# Main.net
KiCad netlist of a schematic drawn in Altium Designer
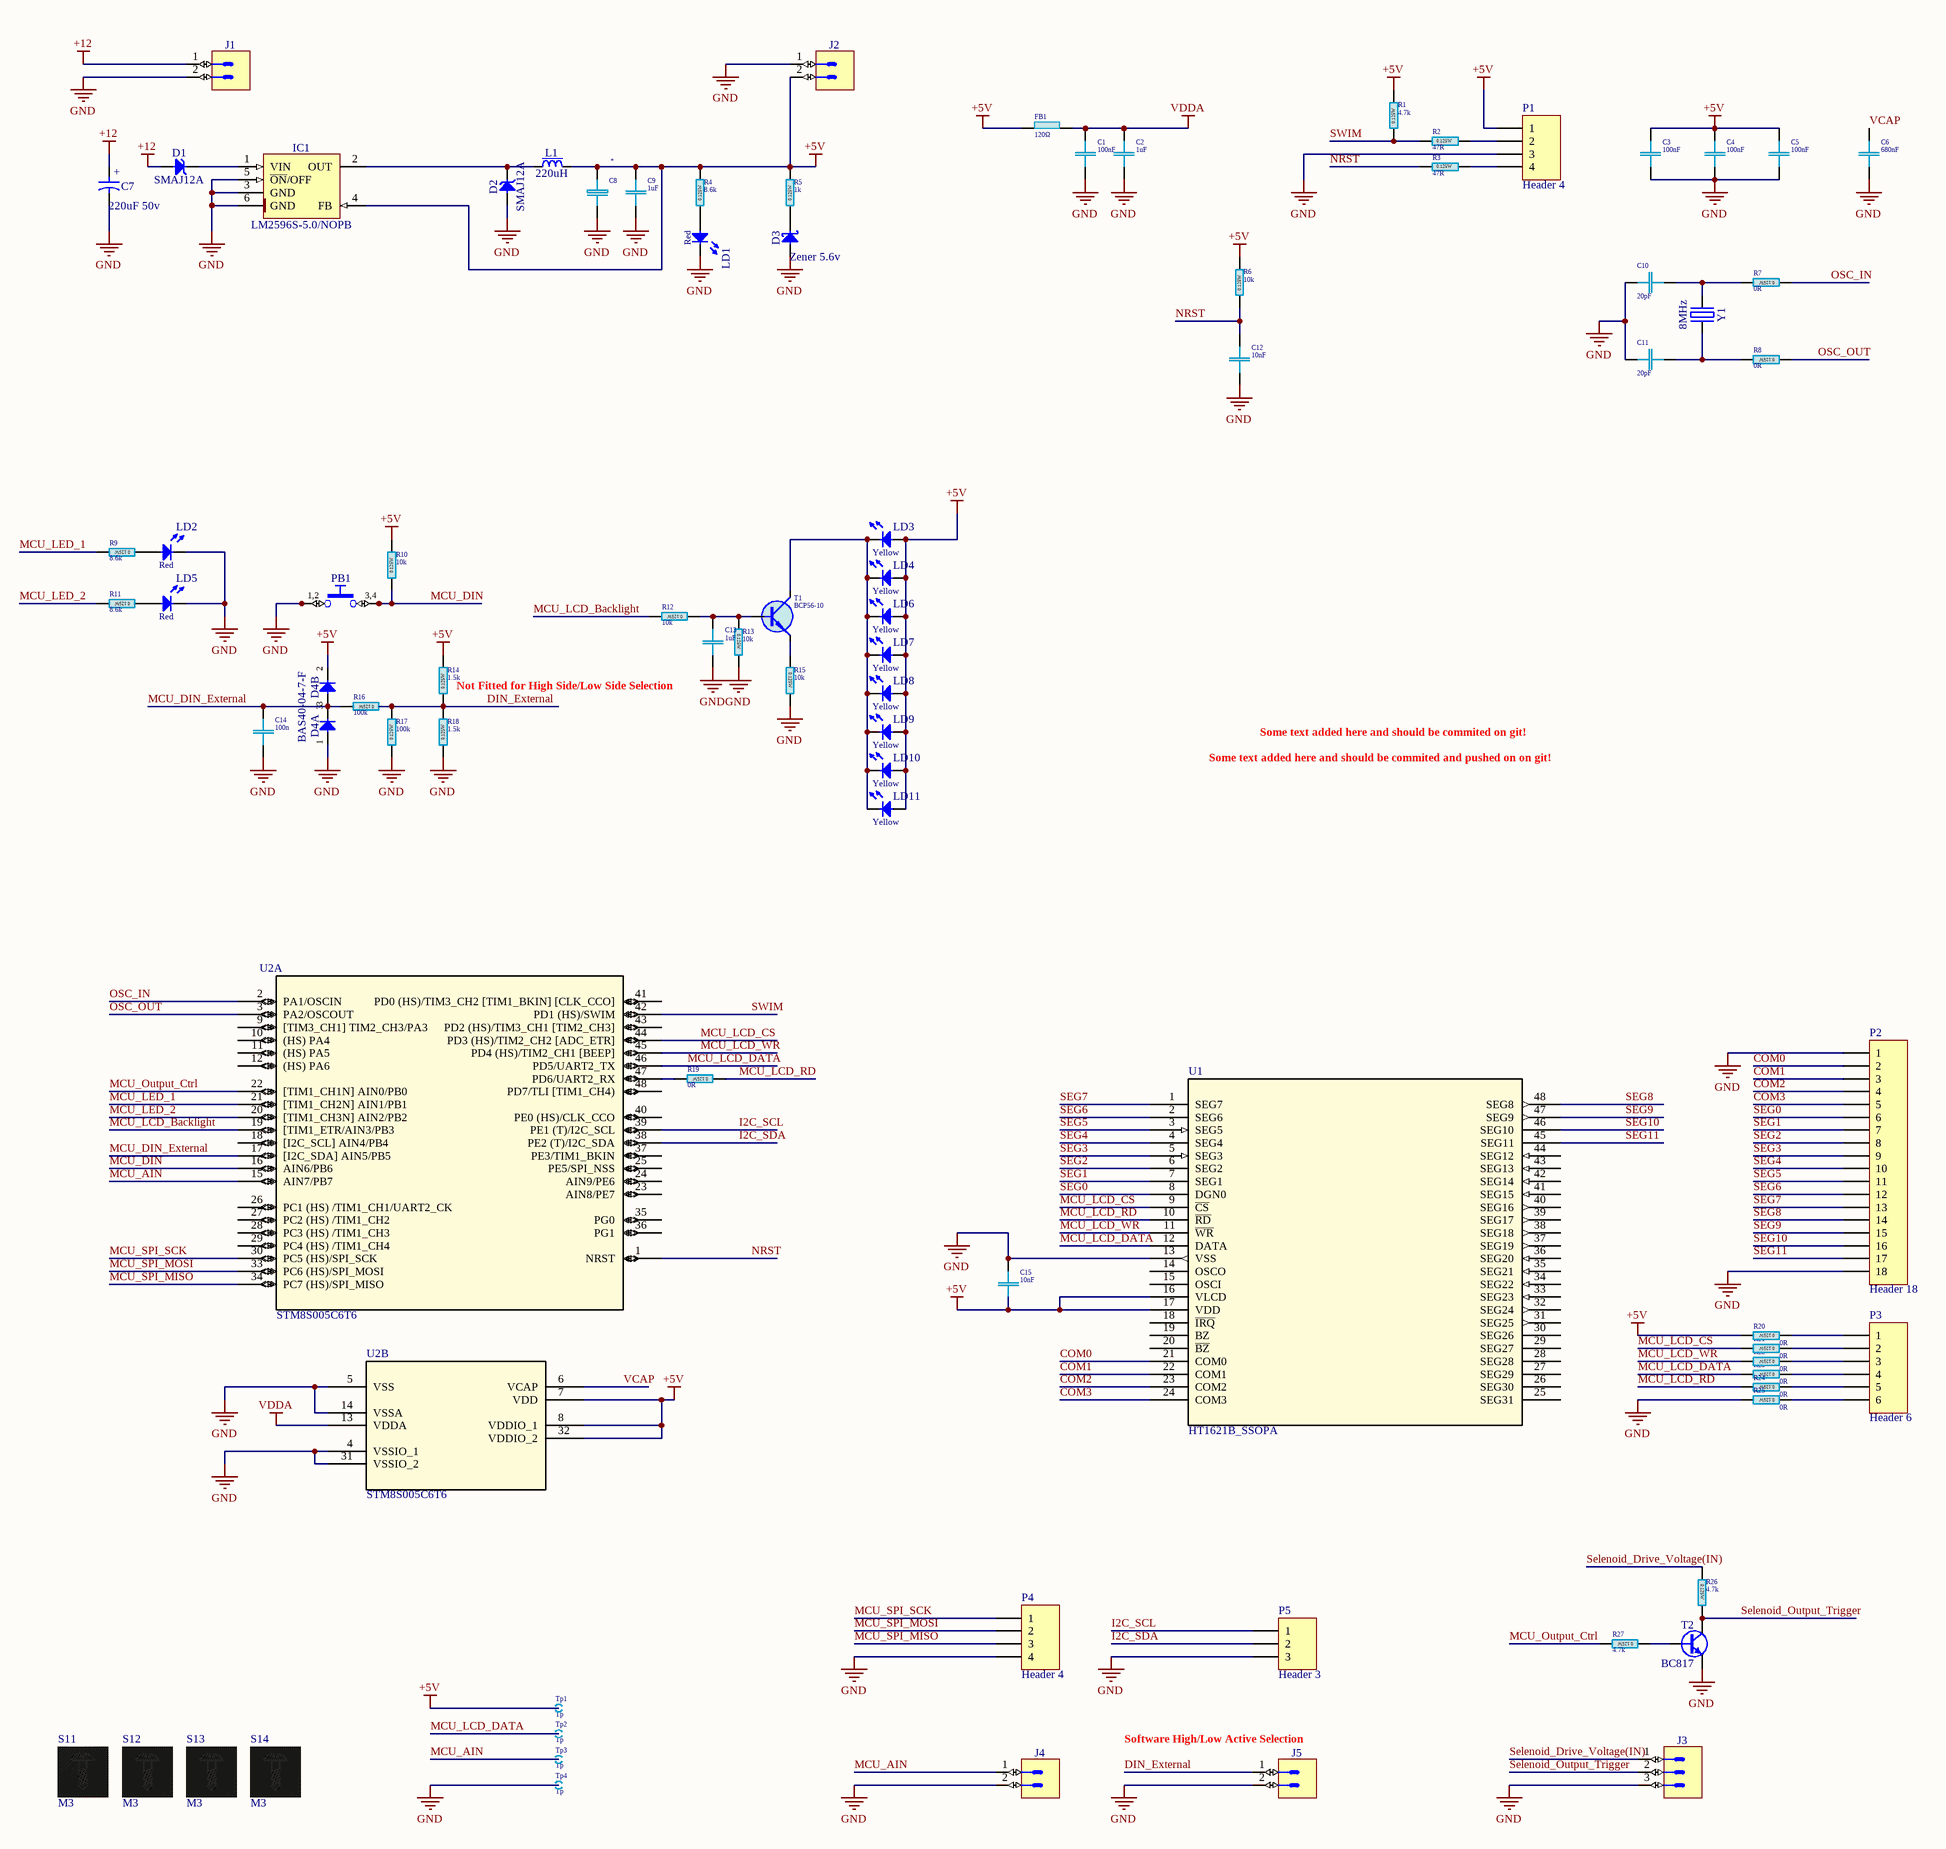
[diagram p0: Main.SchDoc]

(export (version "E")
  (design (tool "Eeschema 10.0.6"))
  (components
    (comp (ref "C1")
      (value "100nF")
      (footprint "C 0805(2012)x0.65")
      (description "SMD 0805     16V X7R 10%")
      (fields (field (name "MANUFACTURER") "Samsung"))
      (libsource (lib "SMD Passive") (part "C 0805    16V X7R - 0*"))
    )
    (comp (ref "C2")
      (value "1uF")
      (footprint "C 0805(2012)x0.65")
      (description "SMD 0805     50V X7R 10%")
      (fields (field (name "PART NUMBER") "CL21B105KBFNNNE") (field (name "MANUFACTURER") "Samsung"))
      (libsource (lib "SMD Passive") (part "C 0805    50V X7R - 1u"))
    )
    (comp (ref "C3")
      (value "100nF")
      (footprint "C 0805(2012)x0.65")
      (description "SMD 0805     16V X7R 10%")
      (fields (field (name "MANUFACTURER") "Samsung"))
      (libsource (lib "SMD Passive") (part "C 0805    16V X7R - 0*"))
    )
    (comp (ref "C4")
      (value "100nF")
      (footprint "C 0805(2012)x0.65")
      (description "SMD 0805     16V X7R 10%")
      (fields (field (name "MANUFACTURER") "Samsung"))
      (libsource (lib "SMD Passive") (part "C 0805    16V X7R - 0*"))
    )
    (comp (ref "C5")
      (value "100nF")
      (footprint "C 0805(2012)x0.65")
      (description "SMD 0805     16V X7R 10%")
      (fields (field (name "MANUFACTURER") "Samsung"))
      (libsource (lib "SMD Passive") (part "C 0805    16V X7R - 0*"))
    )
    (comp (ref "C6")
      (value "680nF")
      (footprint "C 0805(2012)x0.65")
      (description "SMD 0805     16V X7R 10%")
      (fields (field (name "MANUFACTURER") "Samsung"))
      (libsource (lib "SMD Passive") (part "C 0805    16V X7R - 0*"))
    )
    (comp (ref "C7")
      (value "220uF 50v")
      (footprint "CAPAE1030X1020N")
      (description "Polarised capacitor")
      (fields (field (name "PART NUMBER") "CAE1030-1020_220UF_50V_20%") (field (name "VOLTAGE") "50V"))
      (libsource (lib "Capacitors") (part "Capacitor - polarized"))
    )
    (comp (ref "C8")
      (value "*")
      (footprint "EL SMD D8 h10.5")
      (description "SMD D   8mm h10.5mm")
      (fields (field (name "MANUFACTURER") "Fujicon") (field (name "ALTIUM_VALUE") "*"))
      (libsource (lib "SMD Passive") (part "EL D   8mm h10.5mm"))
    )
    (comp (ref "C9")
      (value "1uF")
      (footprint "C 0805(2012)x0.65")
      (description "SMD 0805     50V X7R 10%")
      (fields (field (name "PART NUMBER") "CL21B105KBFNNNE") (field (name "MANUFACTURER") "Samsung"))
      (libsource (lib "SMD Passive") (part "C 0805    50V X7R - 1u"))
    )
    (comp (ref "C10")
      (value "20pF")
      (footprint "C 0805(2012)x0.65")
      (description "SMD 0805     16V X7R 10%")
      (fields (field (name "MANUFACTURER") "Samsung"))
      (libsource (lib "SMD Passive") (part "C 0805    16V X7R - 0*"))
    )
    (comp (ref "C11")
      (value "20pF")
      (footprint "C 0805(2012)x0.65")
      (description "SMD 0805     16V X7R 10%")
      (fields (field (name "MANUFACTURER") "Samsung"))
      (libsource (lib "SMD Passive") (part "C 0805    16V X7R - 0*"))
    )
    (comp (ref "C12")
      (value "10nF")
      (footprint "C 0805(2012)x0.65")
      (description "SMD 0805     16V X7R 10%")
      (fields (field (name "MANUFACTURER") "Samsung"))
      (libsource (lib "SMD Passive") (part "C 0805    16V X7R - 0*"))
    )
    (comp (ref "C13")
      (value "1uF")
      (footprint "C 0805(2012)x0.65")
      (description "SMD 0805     50V X7R 10%")
      (fields (field (name "PART NUMBER") "CL21B105KBFNNNE") (field (name "MANUFACTURER") "Samsung"))
      (libsource (lib "SMD Passive") (part "C 0805    50V X7R - 1u"))
    )
    (comp (ref "C14")
      (value "100n")
      (footprint "C 0805(2012)x0.65")
      (description "SMD 0805     50V X7R 10%")
      (fields (field (name "PART NUMBER") "CL21B105KBFNNNE") (field (name "MANUFACTURER") "Samsung"))
      (libsource (lib "SMD Passive") (part "C 0805    50V X7R - 1u"))
    )
    (comp (ref "C15")
      (value "10nF")
      (footprint "C 0805(2012)x0.65")
      (description "SMD 0805     16V X7R 10%")
      (fields (field (name "MANUFACTURER") "Samsung"))
      (libsource (lib "SMD Passive") (part "C 0805    16V X7R - 0*"))
    )
    (comp (ref "D1")
      (value "SMAJ12A")
      (footprint "DIOM5127X229N")
      (description "Transient Voltage Suppressor Diode (Uni-Directional)")
      (fields (field (name "VOLTAGE") "12V") (field (name "POWER") "20.1A"))
      (libsource (lib "ICs And Semiconductors") (part "Diode TVS Uni-Directional"))
    )
    (comp (ref "D2")
      (value "SMAJ12A")
      (footprint "DIOM5127X229N")
      (description "Transient Voltage Suppressor Diode (Uni-Directional)")
      (fields (field (name "VOLTAGE") "12V") (field (name "POWER") "20.1A"))
      (libsource (lib "ICs And Semiconductors") (part "Diode TVS Uni-Directional"))
    )
    (comp (ref "D3")
      (value "Zener 5.6v")
      (footprint "DIOMELF3515AN")
      (description "Zener 5.6V minimelf")
      (fields (field (name "PART NUMBER") "BAS86-M") (field (name "VOLTAGE") "50V"))
      (libsource (lib "ICs And Semiconductors") (part "Diode Schottky"))
    )
    (comp (ref "D4")
      (value "BAS40-04-7-F")
      (footprint "SOT95P240X110-3N")
      (description "Serial Diode")
      (fields (field (name "VOLTAGE") "40V") (field (name "POWER") "200mA"))
      (libsource (lib "ICs And Semiconductors") (part "Diode x2 A1C3_A3C2"))
    )
    (comp (ref "FB1")
      (value "0.525u")
      (footprint "FB 0805(2012)")
      (description "SMD 0805 1.5A 330Ω/90mΩ")
      (fields
        (field (name "PART NUMBER") "BLM21PG331SN1D")
        (field (name "MANUFACTURER") "Murata")
        (field (name "ZTYP@100MHZ") "120Ω")
      )
      (libsource (lib "SMD Passive") (part "FB BLM21P 330"))
    )
    (comp (ref "IC1")
      (value "LM2596S-5.0/NOPB")
      (footprint "TO170P1435X465-6N-R1041X635")
      (description "SIMPLE SWITCHER® Power Converter 150kHz, 3A Step-Down Voltage Regulator")
      (fields (field (name "MANUFACTURER") "TEXAS INSTRUMENTS"))
      (libsource (lib "ICs And Semiconductors") (part "LM2596"))
    )
    (comp (ref "J1")
      (value "~")
      (footprint "PHOENIX_1803277")
      (description "Connector 2 Male")
      (fields (field (name "PART NUMBER") "PHOENIX_1803277") (field (name "MANUFACTURER") "PHOENIX CONTACT"))
      (libsource (lib "Connectors") (part "Connector 2 Male"))
    )
    (comp (ref "J2")
      (value "~")
      (footprint "PHOENIX_1803277")
      (description "Connector 2 Male")
      (fields (field (name "PART NUMBER") "PHOENIX_1803277") (field (name "MANUFACTURER") "PHOENIX CONTACT"))
      (libsource (lib "Connectors") (part "Connector 2 Male"))
    )
    (comp (ref "J3")
      (value "~")
      (footprint "PHOENIX_1803280")
      (description "Connector 3 Male")
      (fields (field (name "PART NUMBER") "PHOENIX_1803280") (field (name "MANUFACTURER") "PHOENIX CONTACT"))
      (libsource (lib "Connectors") (part "Connector 3 Male"))
    )
    (comp (ref "J4")
      (value "~")
      (footprint "PHOENIX_1803277")
      (description "Connector 2 Male")
      (fields (field (name "PART NUMBER") "PHOENIX_1803277") (field (name "MANUFACTURER") "PHOENIX CONTACT"))
      (libsource (lib "Connectors") (part "Connector 2 Male"))
    )
    (comp (ref "J5")
      (value "~")
      (footprint "PHOENIX_1803277")
      (description "Connector 2 Male")
      (fields (field (name "PART NUMBER") "PHOENIX_1803277") (field (name "MANUFACTURER") "PHOENIX CONTACT"))
      (libsource (lib "Connectors") (part "Connector 2 Male"))
    )
    (comp (ref "L1")
      (value "220uH")
      (footprint "IND_MURATA-PS_8200")
      (description "Inductor With Core")
      (fields (field (name "PART NUMBER") "IND_220UH_10%_MURATA-PS_8200") (field (name "POWER") "100mA"))
      (libsource (lib "Inductors & Transformers") (part "Inductor With Magnetic core"))
    )
    (comp (ref "LD1")
      (value "Red")
      (footprint "LED_ROHM_SML-D12U8WT86")
      (description "LED Red 1C 2A")
      (fields (field (name "PART NUMBER") "LED_ROHM_SML-D12U8WT86") (field (name "MANUFACTURER") "ROHM"))
      (libsource (lib "ICs And Semiconductors") (part "LED Red 1C 2A"))
    )
    (comp (ref "LD2")
      (value "Red")
      (footprint "LED_ROHM_SML-D12U8WT86")
      (description "LED Red 1C 2A")
      (fields (field (name "PART NUMBER") "LED_ROHM_SML-D12U8WT86") (field (name "MANUFACTURER") "ROHM"))
      (libsource (lib "ICs And Semiconductors") (part "LED Red 1C 2A"))
    )
    (comp (ref "LD3")
      (value "Yellow")
      (footprint "LEDM3528X210N_YELLOW")
      (description "LED Yellow 1C 2A")
      (fields (field (name "PART NUMBER") "LED_OSRAM_LYT676-R1S2-26") (field (name "MANUFACTURER") "OSRAM"))
      (libsource (lib "ICs And Semiconductors") (part "LED Yellow 1C 2A"))
    )
    (comp (ref "LD4")
      (value "Yellow")
      (footprint "LEDM3528X210N_YELLOW")
      (description "LED Yellow 1C 2A")
      (fields (field (name "PART NUMBER") "LED_OSRAM_LYT676-R1S2-26") (field (name "MANUFACTURER") "OSRAM"))
      (libsource (lib "ICs And Semiconductors") (part "LED Yellow 1C 2A"))
    )
    (comp (ref "LD5")
      (value "Red")
      (footprint "LED_ROHM_SML-D12U8WT86")
      (description "LED Red 1C 2A")
      (fields (field (name "PART NUMBER") "LED_ROHM_SML-D12U8WT86") (field (name "MANUFACTURER") "ROHM"))
      (libsource (lib "ICs And Semiconductors") (part "LED Red 1C 2A"))
    )
    (comp (ref "LD6")
      (value "Yellow")
      (footprint "LEDM3528X210N_YELLOW")
      (description "LED Yellow 1C 2A")
      (fields (field (name "PART NUMBER") "LED_OSRAM_LYT676-R1S2-26") (field (name "MANUFACTURER") "OSRAM"))
      (libsource (lib "ICs And Semiconductors") (part "LED Yellow 1C 2A"))
    )
    (comp (ref "LD7")
      (value "Yellow")
      (footprint "LEDM3528X210N_YELLOW")
      (description "LED Yellow 1C 2A")
      (fields (field (name "PART NUMBER") "LED_OSRAM_LYT676-R1S2-26") (field (name "MANUFACTURER") "OSRAM"))
      (libsource (lib "ICs And Semiconductors") (part "LED Yellow 1C 2A"))
    )
    (comp (ref "LD8")
      (value "Yellow")
      (footprint "LEDM3528X210N_YELLOW")
      (description "LED Yellow 1C 2A")
      (fields (field (name "PART NUMBER") "LED_OSRAM_LYT676-R1S2-26") (field (name "MANUFACTURER") "OSRAM"))
      (libsource (lib "ICs And Semiconductors") (part "LED Yellow 1C 2A"))
    )
    (comp (ref "LD9")
      (value "Yellow")
      (footprint "LEDM3528X210N_YELLOW")
      (description "LED Yellow 1C 2A")
      (fields (field (name "PART NUMBER") "LED_OSRAM_LYT676-R1S2-26") (field (name "MANUFACTURER") "OSRAM"))
      (libsource (lib "ICs And Semiconductors") (part "LED Yellow 1C 2A"))
    )
    (comp (ref "LD10")
      (value "Yellow")
      (footprint "LEDM3528X210N_YELLOW")
      (description "LED Yellow 1C 2A")
      (fields (field (name "PART NUMBER") "LED_OSRAM_LYT676-R1S2-26") (field (name "MANUFACTURER") "OSRAM"))
      (libsource (lib "ICs And Semiconductors") (part "LED Yellow 1C 2A"))
    )
    (comp (ref "LD11")
      (value "Yellow")
      (footprint "LEDM3528X210N_YELLOW")
      (description "LED Yellow 1C 2A")
      (fields (field (name "PART NUMBER") "LED_OSRAM_LYT676-R1S2-26") (field (name "MANUFACTURER") "OSRAM"))
      (libsource (lib "ICs And Semiconductors") (part "LED Yellow 1C 2A"))
    )
    (comp (ref "P1")
      (value "Header 4")
      (footprint "HDR1X4")
      (description "Header, 4-Pin")
      (libsource (lib "Miscellaneous Connectors") (part "Header 4"))
    )
    (comp (ref "P2")
      (value "Header 18")
      (footprint "HDR1X18")
      (description "Header, 18-Pin")
      (libsource (lib "Miscellaneous Connectors") (part "Header 18"))
    )
    (comp (ref "P3")
      (value "Header 6")
      (footprint "HDR1X6")
      (description "Header, 6-Pin")
      (libsource (lib "Miscellaneous Connectors") (part "Header 6"))
    )
    (comp (ref "P4")
      (value "Header 4")
      (footprint "HDR1X4")
      (description "Header, 4-Pin")
      (libsource (lib "Miscellaneous Connectors") (part "Header 4"))
    )
    (comp (ref "P5")
      (value "Header 3")
      (footprint "HDR1X3")
      (description "Header, 3-Pin")
      (libsource (lib "Miscellaneous Connectors") (part "Header 3"))
    )
    (comp (ref "PB1")
      (value "Push Button")
      (footprint "PB_TYCO_FSM2JSMA")
      (description "Push-Button Switch SPDT")
      (fields
        (field (name "PART NUMBER") "PB_TYCO_FSM2JSMA")
        (field (name "MANUFACTURER") "TYCO ELECTRONICS")
      )
      (libsource (lib "Eletro-mechanical") (part "PB SPST 12NO-34NO"))
    )
    (comp (ref "R1")
      (value "4.7k")
      (footprint "R 0805(2012)")
      (description "SMD 0805 0.125W 5% 150V")
      (fields (field (name "MANUFACTURER") "YAGEO") (field (name "POWER") "0.125W"))
      (libsource (lib "SMD Passive") (part "R 0805-5%"))
    )
    (comp (ref "R2")
      (value "47R")
      (footprint "R 0805(2012)")
      (description "SMD 0805 0.125W 5% 150V")
      (fields (field (name "MANUFACTURER") "YAGEO") (field (name "POWER") "0.125W"))
      (libsource (lib "") (part "R 0805-5%_3"))
    )
    (comp (ref "R3")
      (value "47R")
      (footprint "R 0805(2012)")
      (description "SMD 0805 0.125W 5% 150V")
      (fields (field (name "MANUFACTURER") "YAGEO") (field (name "POWER") "0.125W"))
      (libsource (lib "") (part "R 0805-5%_3"))
    )
    (comp (ref "R4")
      (value "8.6k")
      (footprint "R 0805(2012)")
      (description "SMD 0805 0.125W 5% 150V")
      (fields (field (name "MANUFACTURER") "YAGEO") (field (name "POWER") "0.125W"))
      (libsource (lib "SMD Passive") (part "R 0805-5%"))
    )
    (comp (ref "R5")
      (value "1k")
      (footprint "R 0805(2012)")
      (description "SMD 0805 0.125W 5% 150V")
      (fields (field (name "MANUFACTURER") "YAGEO") (field (name "POWER") "0.125W"))
      (libsource (lib "SMD Passive") (part "R 0805-5%"))
    )
    (comp (ref "R6")
      (value "10k")
      (footprint "R 0805(2012)")
      (description "SMD 0805 0.125W 5% 150V")
      (fields (field (name "MANUFACTURER") "YAGEO") (field (name "POWER") "0.125W"))
      (libsource (lib "SMD Passive") (part "R 0805-5%"))
    )
    (comp (ref "R7")
      (value "0R")
      (footprint "R 0805(2012)")
      (description "SMD 0805 0.125W 5% 150V")
      (fields (field (name "MANUFACTURER") "YAGEO") (field (name "POWER") "0.125W"))
      (libsource (lib "") (part "R 0805-5%_1"))
    )
    (comp (ref "R8")
      (value "0R")
      (footprint "R 0805(2012)")
      (description "SMD 0805 0.125W 5% 150V")
      (fields (field (name "MANUFACTURER") "YAGEO") (field (name "POWER") "0.125W"))
      (libsource (lib "") (part "R 0805-5%_1"))
    )
    (comp (ref "R9")
      (value "8.6k")
      (footprint "R 0805(2012)")
      (description "SMD 0805 0.125W 5% 150V")
      (fields (field (name "MANUFACTURER") "YAGEO") (field (name "POWER") "0.125W"))
      (libsource (lib "") (part "R 0805-5%_1"))
    )
    (comp (ref "R10")
      (value "10k")
      (footprint "R 0805(2012)")
      (description "SMD 0805 0.125W 5% 150V")
      (fields (field (name "MANUFACTURER") "YAGEO") (field (name "POWER") "0.125W"))
      (libsource (lib "SMD Passive") (part "R 0805-5%"))
    )
    (comp (ref "R11")
      (value "8.6k")
      (footprint "R 0805(2012)")
      (description "SMD 0805 0.125W 5% 150V")
      (fields (field (name "MANUFACTURER") "YAGEO") (field (name "POWER") "0.125W"))
      (libsource (lib "") (part "R 0805-5%_1"))
    )
    (comp (ref "R12")
      (value "10k")
      (footprint "R 0805(2012)")
      (description "SMD 0805 0.125W 5% 150V")
      (fields (field (name "MANUFACTURER") "YAGEO") (field (name "POWER") "0.125W"))
      (libsource (lib "") (part "R 0805-5%_1"))
    )
    (comp (ref "R13")
      (value "10k")
      (footprint "R 0805(2012)")
      (description "SMD 0805 0.125W 5% 150V")
      (fields (field (name "MANUFACTURER") "YAGEO") (field (name "POWER") "0.125W"))
      (libsource (lib "") (part "R 0805-5%_2"))
    )
    (comp (ref "R14")
      (value "1.5k")
      (footprint "R 0805(2012)")
      (description "SMD 0805 0.125W 5% 150V")
      (fields (field (name "MANUFACTURER") "YAGEO") (field (name "POWER") "0.125W"))
      (libsource (lib "SMD Passive") (part "R 0805-5%"))
    )
    (comp (ref "R15")
      (value "10k")
      (footprint "R 0805(2012)")
      (description "SMD 0805 0.125W 5% 150V")
      (fields (field (name "MANUFACTURER") "YAGEO") (field (name "POWER") "0.125W"))
      (libsource (lib "") (part "R 0805-5%_2"))
    )
    (comp (ref "R16")
      (value "100k")
      (footprint "R 0805(2012)")
      (description "SMD 0805 0.125W 5% 150V")
      (fields (field (name "MANUFACTURER") "YAGEO") (field (name "POWER") "0.125W"))
      (libsource (lib "") (part "R 0805-5%_1"))
    )
    (comp (ref "R17")
      (value "100k")
      (footprint "R 0805(2012)")
      (description "SMD 0805 0.125W 5% 150V")
      (fields (field (name "MANUFACTURER") "YAGEO") (field (name "POWER") "0.125W"))
      (libsource (lib "SMD Passive") (part "R 0805-5%"))
    )
    (comp (ref "R18")
      (value "1.5k")
      (footprint "R 0805(2012)")
      (description "SMD 0805 0.125W 5% 150V")
      (fields (field (name "MANUFACTURER") "YAGEO") (field (name "POWER") "0.125W"))
      (libsource (lib "SMD Passive") (part "R 0805-5%"))
    )
    (comp (ref "R19")
      (value "0R")
      (footprint "R 0805(2012)")
      (description "SMD 0805 0.125W 5% 150V")
      (fields (field (name "MANUFACTURER") "YAGEO") (field (name "POWER") "0.125W"))
      (libsource (lib "") (part "R 0805-5%_1"))
    )
    (comp (ref "R20")
      (value "0R")
      (footprint "R 0805(2012)")
      (description "SMD 0805 0.125W 5% 150V")
      (fields (field (name "MANUFACTURER") "YAGEO") (field (name "POWER") "0.125W"))
      (libsource (lib "") (part "R 0805-5%_1"))
    )
    (comp (ref "R21")
      (value "0R")
      (footprint "R 0805(2012)")
      (description "SMD 0805 0.125W 5% 150V")
      (fields (field (name "MANUFACTURER") "YAGEO") (field (name "POWER") "0.125W"))
      (libsource (lib "") (part "R 0805-5%_1"))
    )
    (comp (ref "R22")
      (value "0R")
      (footprint "R 0805(2012)")
      (description "SMD 0805 0.125W 5% 150V")
      (fields (field (name "MANUFACTURER") "YAGEO") (field (name "POWER") "0.125W"))
      (libsource (lib "") (part "R 0805-5%_1"))
    )
    (comp (ref "R23")
      (value "0R")
      (footprint "R 0805(2012)")
      (description "SMD 0805 0.125W 5% 150V")
      (fields (field (name "MANUFACTURER") "YAGEO") (field (name "POWER") "0.125W"))
      (libsource (lib "") (part "R 0805-5%_1"))
    )
    (comp (ref "R24")
      (value "0R")
      (footprint "R 0805(2012)")
      (description "SMD 0805 0.125W 5% 150V")
      (fields (field (name "MANUFACTURER") "YAGEO") (field (name "POWER") "0.125W"))
      (libsource (lib "") (part "R 0805-5%_1"))
    )
    (comp (ref "R25")
      (value "0R")
      (footprint "R 0805(2012)")
      (description "SMD 0805 0.125W 5% 150V")
      (fields (field (name "MANUFACTURER") "YAGEO") (field (name "POWER") "0.125W"))
      (libsource (lib "") (part "R 0805-5%_1"))
    )
    (comp (ref "R26")
      (value "4.7k")
      (footprint "R 0805(2012)")
      (description "SMD 0805 0.125W 5% 150V")
      (fields (field (name "MANUFACTURER") "YAGEO") (field (name "POWER") "0.125W"))
      (libsource (lib "") (part "R 0805-5%_2"))
    )
    (comp (ref "R27")
      (value "4.7k")
      (footprint "R 0805(2012)")
      (description "SMD 0805 0.125W 5% 150V")
      (fields (field (name "MANUFACTURER") "YAGEO") (field (name "POWER") "0.125W"))
      (libsource (lib "") (part "R 0805-5%_1"))
    )
    (comp (ref "S11") (value "M3") (footprint "PCBComponent_1") (libsource (lib "Screw_M3") (part "Screw")))
    (comp (ref "S12") (value "M3") (footprint "PCBComponent_1") (libsource (lib "Screw_M3") (part "Screw")))
    (comp (ref "S13") (value "M3") (footprint "PCBComponent_1") (libsource (lib "Screw_M3") (part "Screw")))
    (comp (ref "S14") (value "M3") (footprint "PCBComponent_1") (libsource (lib "Screw_M3") (part "Screw")))
    (comp (ref "T1")
      (value "BCP56-10")
      (footprint "SOT223")
      (description "SOT89    80V 1A 180MHz   6pF")
      (fields (field (name "PART NUMBER") "BCP5610TA") (field (name "MANUFACTURER") "ROHm"))
      (libsource (lib "BJT") (part "BCP56-10"))
    )
    (comp (ref "T2")
      (value "BC817")
      (footprint "SOT95P230X110-3N")
      (description "NPN Transistor")
      (fields (field (name "MANUFACTURER") "NXP SEMICONDUCTORS"))
      (libsource (lib "ICs And Semiconductors") (part "NPN B1 E2 C3"))
    )
    (comp (ref "Tp1")
      (value "Tp")
      (footprint "Tp-0.7")
      (description "TestPoint")
      (libsource (lib "SMD Passive") (part "Tp"))
    )
    (comp (ref "Tp2")
      (value "Tp")
      (footprint "Tp-0.7")
      (description "TestPoint")
      (libsource (lib "SMD Passive") (part "Tp"))
    )
    (comp (ref "Tp3")
      (value "Tp")
      (footprint "Tp-0.7")
      (description "TestPoint")
      (libsource (lib "SMD Passive") (part "Tp"))
    )
    (comp (ref "Tp4")
      (value "Tp")
      (footprint "Tp-0.7")
      (description "TestPoint")
      (libsource (lib "SMD Passive") (part "Tp"))
    )
    (comp (ref "U1")
      (value "HT1621B_SSOPA")
      (footprint "DL48")
      (description "No Description Available")
      (fields (field (name "MANUFACTURER_PART_NUMBER") "DAC7634E"))
      (libsource (lib "DAC7634E") (part "DAC7634E"))
    )
    (comp (ref "U2")
      (value "STM8S005C6T6")
      (footprint "LQFP48-7X7mm")
      (description "No Description Available")
      (libsource (lib "STM8S005C6T6") (part "STM8S005C6T6"))
    )
    (comp (ref "Y1")
      (value "8MHz")
      (footprint "XTAL1160X490X430")
      (description "Quartz Crystal")
      (fields
        (field (name "PART NUMBER") "XTAL_10MHZ_IQD_LFXTAL003166")
        (field (name "MANUFACTURER") "IQD FREQUENCY PRODUCTS")
      )
      (libsource (lib "ICs And Semiconductors") (part "Quartz Crystal"))
    )
  )
  (nets
    (net (code "1") (name "+5V") (class "Default")
      (node (ref "C15") (pin "2") (pinfunction "2_2") (pintype "passive"))
      (node (ref "C3") (pin "2") (pinfunction "2_2") (pintype "passive"))
      (node (ref "C4") (pin "2") (pinfunction "2_2") (pintype "passive"))
      (node (ref "C5") (pin "2") (pinfunction "2_2") (pintype "passive"))
      (node (ref "C8") (pin "1") (pinfunction "1_1") (pintype "passive"))
      (node (ref "C9") (pin "1") (pinfunction "1_1") (pintype "passive"))
      (node (ref "D4") (pin "2") (pinfunction "C_2") (pintype "passive"))
      (node (ref "FB1") (pin "1") (pinfunction "1_1") (pintype "passive"))
      (node (ref "IC1") (pin "4") (pinfunction "FB_4") (pintype "input"))
      (node (ref "J2") (pin "2") (pinfunction "2_2") (pintype "bidirectional"))
      (node (ref "L1") (pin "2") (pinfunction "2_2") (pintype "passive"))
      (node (ref "LD10") (pin "2") (pinfunction "A_2") (pintype "passive"))
      (node (ref "LD11") (pin "2") (pinfunction "A_2") (pintype "passive"))
      (node (ref "LD3") (pin "2") (pinfunction "A_2") (pintype "passive"))
      (node (ref "LD4") (pin "2") (pinfunction "A_2") (pintype "passive"))
      (node (ref "LD6") (pin "2") (pinfunction "A_2") (pintype "passive"))
      (node (ref "LD7") (pin "2") (pinfunction "A_2") (pintype "passive"))
      (node (ref "LD8") (pin "2") (pinfunction "A_2") (pintype "passive"))
      (node (ref "LD9") (pin "2") (pinfunction "A_2") (pintype "passive"))
      (node (ref "P1") (pin "1") (pinfunction "1_1") (pintype "passive"))
      (node (ref "R1") (pin "2") (pinfunction "2_2") (pintype "passive"))
      (node (ref "R10") (pin "2") (pinfunction "2_2") (pintype "passive"))
      (node (ref "R14") (pin "2") (pinfunction "2_2") (pintype "passive"))
      (node (ref "R20") (pin "2") (pinfunction "2_2") (pintype "passive"))
      (node (ref "R4") (pin "2") (pinfunction "2_2") (pintype "passive"))
      (node (ref "R5") (pin "2") (pinfunction "2_2") (pintype "passive"))
      (node (ref "R6") (pin "2") (pinfunction "2_2") (pintype "passive"))
      (node (ref "Tp1") (pin "1") (pinfunction "1_1") (pintype "passive"))
      (node (ref "U1") (pin "16") (pinfunction "VLCD_16") (pintype "power_in"))
      (node (ref "U1") (pin "17") (pinfunction "VDD_17") (pintype "passive"))
      (node (ref "U2") (pin "32") (pinfunction "VDDIO_2_32") (pintype "power_in"))
      (node (ref "U2") (pin "7") (pinfunction "VDD_7") (pintype "power_in"))
      (node (ref "U2") (pin "8") (pinfunction "VDDIO_1_8") (pintype "power_in"))
    )
    (net (code "2") (name "+12") (class "Default")
      (node (ref "C7") (pin "1") (pinfunction "1_1") (pintype "passive"))
      (node (ref "D1") (pin "2") (pinfunction "A_2") (pintype "passive"))
      (node (ref "J1") (pin "1") (pinfunction "1_1") (pintype "bidirectional"))
    )
    (net (code "3") (name "/COM0") (class "Default")
      (node (ref "P2") (pin "2") (pinfunction "2_2") (pintype "passive"))
      (node (ref "U1") (pin "21") (pinfunction "COM0_21") (pintype "power_in"))
    )
    (net (code "4") (name "/COM1") (class "Default")
      (node (ref "P2") (pin "3") (pinfunction "3_3") (pintype "passive"))
      (node (ref "U1") (pin "22") (pinfunction "COM1_22") (pintype "power_in"))
    )
    (net (code "5") (name "/COM2") (class "Default")
      (node (ref "P2") (pin "4") (pinfunction "4_4") (pintype "passive"))
      (node (ref "U1") (pin "23") (pinfunction "COM2_23") (pintype "power_in"))
    )
    (net (code "6") (name "/COM3") (class "Default")
      (node (ref "P2") (pin "5") (pinfunction "5_5") (pintype "passive"))
      (node (ref "U1") (pin "24") (pinfunction "COM3_24") (pintype "power_in"))
    )
    (net (code "7") (name "/DIN_External") (class "Default")
      (node (ref "J5") (pin "1") (pinfunction "1_1") (pintype "bidirectional"))
      (node (ref "R14") (pin "1") (pinfunction "1_1") (pintype "passive"))
      (node (ref "R16") (pin "1") (pinfunction "1_1") (pintype "passive"))
      (node (ref "R17") (pin "2") (pinfunction "2_2") (pintype "passive"))
      (node (ref "R18") (pin "2") (pinfunction "2_2") (pintype "passive"))
    )
    (net (code "8") (name "/I2C_SCL") (class "Default")
      (node (ref "P5") (pin "1") (pinfunction "1_1") (pintype "passive"))
      (node (ref "U2") (pin "39") (pinfunction "PE1_(T)/I2C_SCL_39") (pintype "bidirectional"))
    )
    (net (code "9") (name "/I2C_SDA") (class "Default")
      (node (ref "P5") (pin "2") (pinfunction "2_2") (pintype "passive"))
      (node (ref "U2") (pin "38") (pinfunction "PE2_(T)/I2C_SDA_38") (pintype "bidirectional"))
    )
    (net (code "10") (name "/MCU_AIN") (class "Default")
      (node (ref "J4") (pin "1") (pinfunction "1_1") (pintype "bidirectional"))
      (node (ref "Tp3") (pin "1") (pinfunction "1_1") (pintype "passive"))
      (node (ref "U2") (pin "15") (pinfunction "AIN7/PB7_15") (pintype "bidirectional"))
    )
    (net (code "11") (name "/MCU_DIN") (class "Default")
      (node (ref "PB1") (pin "3") (pinfunction "3_3") (pintype "bidirectional"))
      (node (ref "PB1") (pin "4") (pinfunction "4_4") (pintype "bidirectional"))
      (node (ref "R10") (pin "1") (pinfunction "1_1") (pintype "passive"))
      (node (ref "U2") (pin "16") (pinfunction "AIN6/PB6_16") (pintype "bidirectional"))
    )
    (net (code "12") (name "/MCU_DIN_External") (class "Default")
      (node (ref "C14") (pin "1") (pinfunction "1_1") (pintype "passive"))
      (node (ref "D4") (pin "3") (pinfunction "COMAC_3") (pintype "passive"))
      (node (ref "R16") (pin "2") (pinfunction "2_2") (pintype "passive"))
      (node (ref "U2") (pin "17") (pinfunction "[I2C_SDA]_AIN5/PB5_17") (pintype "bidirectional"))
    )
    (net (code "13") (name "/MCU_LCD_Backlight") (class "Default")
      (node (ref "R12") (pin "2") (pinfunction "2_2") (pintype "passive"))
      (node (ref "U2") (pin "19") (pinfunction "[TIM1_ETR/AIN3/PB3_19") (pintype "bidirectional"))
    )
    (net (code "14") (name "/MCU_LCD_CS") (class "Default")
      (node (ref "R21") (pin "2") (pinfunction "2_2") (pintype "passive"))
      (node (ref "U1") (pin "9") (pinfunction "~{CS}_9") (pintype "passive"))
      (node (ref "U2") (pin "44") (pinfunction "PD3_(HS)/TIM2_CH2_[ADC_ETR]_44") (pintype "bidirectional"))
    )
    (net (code "15") (name "/MCU_LCD_DATA") (class "Default")
      (node (ref "R23") (pin "2") (pinfunction "2_2") (pintype "passive"))
      (node (ref "Tp2") (pin "1") (pinfunction "1_1") (pintype "passive"))
      (node (ref "U1") (pin "12") (pinfunction "DATA_12") (pintype "power_in"))
      (node (ref "U2") (pin "46") (pinfunction "PD5/UART2_TX_46") (pintype "bidirectional"))
    )
    (net (code "16") (name "/MCU_LCD_RD") (class "Default")
      (node (ref "R19") (pin "1") (pinfunction "1_1") (pintype "passive"))
      (node (ref "R24") (pin "2") (pinfunction "2_2") (pintype "passive"))
      (node (ref "U1") (pin "10") (pinfunction "~{RD}_10") (pintype "power_in"))
    )
    (net (code "17") (name "/MCU_LCD_WR") (class "Default")
      (node (ref "R22") (pin "2") (pinfunction "2_2") (pintype "passive"))
      (node (ref "U1") (pin "11") (pinfunction "~{WR}_11") (pintype "passive"))
      (node (ref "U2") (pin "45") (pinfunction "PD4_(HS)/TIM2_CH1_[BEEP]_45") (pintype "bidirectional"))
    )
    (net (code "18") (name "/MCU_LED_1") (class "Default")
      (node (ref "R9") (pin "2") (pinfunction "2_2") (pintype "passive"))
      (node (ref "U2") (pin "21") (pinfunction "[TIM1_CH2N]_AIN1/PB1_21") (pintype "bidirectional"))
    )
    (net (code "19") (name "/MCU_LED_2") (class "Default")
      (node (ref "R11") (pin "2") (pinfunction "2_2") (pintype "passive"))
      (node (ref "U2") (pin "20") (pinfunction "[TIM1_CH3N]_AIN2/PB2_20") (pintype "bidirectional"))
    )
    (net (code "20") (name "/MCU_Output_Ctrl") (class "Default")
      (node (ref "R27") (pin "2") (pinfunction "2_2") (pintype "passive"))
      (node (ref "U2") (pin "22") (pinfunction "[TIM1_CH1N]_AIN0/PB0_22") (pintype "bidirectional"))
    )
    (net (code "21") (name "/MCU_SPI_MISO") (class "Default")
      (node (ref "P4") (pin "3") (pinfunction "3_3") (pintype "passive"))
      (node (ref "U2") (pin "34") (pinfunction "PC7_(HS)/SPI_MISO_34") (pintype "bidirectional"))
    )
    (net (code "22") (name "/MCU_SPI_MOSI") (class "Default")
      (node (ref "P4") (pin "2") (pinfunction "2_2") (pintype "passive"))
      (node (ref "U2") (pin "33") (pinfunction "PC6_(HS)/SPI_MOSI_33") (pintype "bidirectional"))
    )
    (net (code "23") (name "/MCU_SPI_SCK") (class "Default")
      (node (ref "P4") (pin "1") (pinfunction "1_1") (pintype "passive"))
      (node (ref "U2") (pin "30") (pinfunction "PC5_(HS)/SPI_SCK_30") (pintype "bidirectional"))
    )
    (net (code "24") (name "/NRST") (class "Default")
      (node (ref "C12") (pin "1") (pinfunction "1_1") (pintype "passive"))
      (node (ref "R3") (pin "1") (pinfunction "1_1") (pintype "passive"))
      (node (ref "R6") (pin "1") (pinfunction "1_1") (pintype "passive"))
      (node (ref "U2") (pin "1") (pinfunction "NRST_1") (pintype "bidirectional"))
    )
    (net (code "25") (name "/OSC_IN") (class "Default")
      (node (ref "R7") (pin "1") (pinfunction "1_1") (pintype "passive"))
      (node (ref "U2") (pin "2") (pinfunction "PA1/OSCIN_2") (pintype "bidirectional"))
    )
    (net (code "26") (name "/OSC_OUT") (class "Default")
      (node (ref "R8") (pin "1") (pinfunction "1_1") (pintype "passive"))
      (node (ref "U2") (pin "3") (pinfunction "PA2/OSCOUT_3") (pintype "bidirectional"))
    )
    (net (code "27") (name "/SEG0") (class "Default")
      (node (ref "P2") (pin "6") (pinfunction "6_6") (pintype "passive"))
      (node (ref "U1") (pin "8") (pinfunction "DGN0_8") (pintype "power_in"))
    )
    (net (code "28") (name "/SEG1") (class "Default")
      (node (ref "P2") (pin "7") (pinfunction "7_7") (pintype "passive"))
      (node (ref "U1") (pin "7") (pinfunction "SEG1_7") (pintype "passive"))
    )
    (net (code "29") (name "/SEG2") (class "Default")
      (node (ref "P2") (pin "8") (pinfunction "8_8") (pintype "passive"))
      (node (ref "U1") (pin "6") (pinfunction "SEG2_6") (pintype "power_in"))
    )
    (net (code "30") (name "/SEG3") (class "Default")
      (node (ref "P2") (pin "9") (pinfunction "9_9") (pintype "passive"))
      (node (ref "U1") (pin "5") (pinfunction "SEG3_5") (pintype "input"))
    )
    (net (code "31") (name "/SEG4") (class "Default")
      (node (ref "P2") (pin "10") (pinfunction "10_10") (pintype "passive"))
      (node (ref "U1") (pin "4") (pinfunction "SEG4_4") (pintype "power_in"))
    )
    (net (code "32") (name "/SEG5") (class "Default")
      (node (ref "P2") (pin "11") (pinfunction "11_11") (pintype "passive"))
      (node (ref "U1") (pin "3") (pinfunction "SEG5_3") (pintype "input"))
    )
    (net (code "33") (name "/SEG6") (class "Default")
      (node (ref "P2") (pin "12") (pinfunction "12_12") (pintype "passive"))
      (node (ref "U1") (pin "2") (pinfunction "SEG6_2") (pintype "passive"))
    )
    (net (code "34") (name "/SEG7") (class "Default")
      (node (ref "P2") (pin "13") (pinfunction "13_13") (pintype "passive"))
      (node (ref "U1") (pin "1") (pinfunction "SEG7_1") (pintype "passive"))
    )
    (net (code "35") (name "/SEG8") (class "Default")
      (node (ref "P2") (pin "14") (pinfunction "14_14") (pintype "passive"))
      (node (ref "U1") (pin "48") (pinfunction "SEG8_48") (pintype "output"))
    )
    (net (code "36") (name "/SEG9") (class "Default")
      (node (ref "P2") (pin "15") (pinfunction "15_15") (pintype "passive"))
      (node (ref "U1") (pin "47") (pinfunction "SEG9_47") (pintype "output"))
    )
    (net (code "37") (name "/SEG10") (class "Default")
      (node (ref "P2") (pin "16") (pinfunction "16_16") (pintype "passive"))
      (node (ref "U1") (pin "46") (pinfunction "SEG10_46") (pintype "power_in"))
    )
    (net (code "38") (name "/SEG11") (class "Default")
      (node (ref "P2") (pin "17") (pinfunction "17_17") (pintype "passive"))
      (node (ref "U1") (pin "45") (pinfunction "SEG11_45") (pintype "power_in"))
    )
    (net (code "39") (name "/SWIM") (class "Default")
      (node (ref "R1") (pin "1") (pinfunction "1_1") (pintype "passive"))
      (node (ref "R2") (pin "1") (pinfunction "1_1") (pintype "passive"))
      (node (ref "U2") (pin "42") (pinfunction "PD1_(HS)/SWIM_42") (pintype "bidirectional"))
    )
    (net (code "40") (name "/Selenoid_Drive_Voltage(IN)") (class "Default")
      (node (ref "J3") (pin "1") (pinfunction "1_1") (pintype "bidirectional"))
      (node (ref "R26") (pin "1") (pinfunction "1_1") (pintype "passive"))
    )
    (net (code "41") (name "/Selenoid_Output_Trigger") (class "Default")
      (node (ref "J3") (pin "2") (pinfunction "2_2") (pintype "bidirectional"))
      (node (ref "R26") (pin "2") (pinfunction "2_2") (pintype "passive"))
      (node (ref "T2") (pin "3") (pinfunction "C_3") (pintype "passive"))
    )
    (net (code "42") (name "/VCAP") (class "Default")
      (node (ref "C6") (pin "2") (pinfunction "2_2") (pintype "passive"))
      (node (ref "U2") (pin "6") (pinfunction "VCAP_6") (pintype "power_in"))
    )
    (net (code "43") (name "GND") (class "Default")
      (node (ref "C1") (pin "2") (pinfunction "2_2") (pintype "passive"))
      (node (ref "C10") (pin "1") (pinfunction "1_1") (pintype "passive"))
      (node (ref "C11") (pin "1") (pinfunction "1_1") (pintype "passive"))
      (node (ref "C12") (pin "2") (pinfunction "2_2") (pintype "passive"))
      (node (ref "C13") (pin "2") (pinfunction "2_2") (pintype "passive"))
      (node (ref "C14") (pin "2") (pinfunction "2_2") (pintype "passive"))
      (node (ref "C15") (pin "1") (pinfunction "1_1") (pintype "passive"))
      (node (ref "C2") (pin "2") (pinfunction "2_2") (pintype "passive"))
      (node (ref "C3") (pin "1") (pinfunction "1_1") (pintype "passive"))
      (node (ref "C4") (pin "1") (pinfunction "1_1") (pintype "passive"))
      (node (ref "C5") (pin "1") (pinfunction "1_1") (pintype "passive"))
      (node (ref "C6") (pin "1") (pinfunction "1_1") (pintype "passive"))
      (node (ref "C7") (pin "2") (pinfunction "2_2") (pintype "passive"))
      (node (ref "C8") (pin "2") (pinfunction "2_2") (pintype "passive"))
      (node (ref "C9") (pin "2") (pinfunction "2_2") (pintype "passive"))
      (node (ref "D2") (pin "2") (pinfunction "A_2") (pintype "passive"))
      (node (ref "D3") (pin "2") (pinfunction "A_2") (pintype "passive"))
      (node (ref "D4") (pin "1") (pinfunction "A_1") (pintype "passive"))
      (node (ref "IC1") (pin "3") (pinfunction "GND_3") (pintype "power_in"))
      (node (ref "IC1") (pin "5") (pinfunction "~{ON}/OFF_5") (pintype "input"))
      (node (ref "IC1") (pin "6") (pinfunction "GND_6") (pintype "power_in"))
      (node (ref "J1") (pin "2") (pinfunction "2_2") (pintype "bidirectional"))
      (node (ref "J2") (pin "1") (pinfunction "1_1") (pintype "bidirectional"))
      (node (ref "J3") (pin "3") (pinfunction "3_3") (pintype "bidirectional"))
      (node (ref "J4") (pin "2") (pinfunction "2_2") (pintype "bidirectional"))
      (node (ref "J5") (pin "2") (pinfunction "2_2") (pintype "bidirectional"))
      (node (ref "LD1") (pin "1") (pinfunction "C_1") (pintype "passive"))
      (node (ref "LD2") (pin "1") (pinfunction "C_1") (pintype "passive"))
      (node (ref "LD5") (pin "1") (pinfunction "C_1") (pintype "passive"))
      (node (ref "P1") (pin "3") (pinfunction "3_3") (pintype "passive"))
      (node (ref "P2") (pin "1") (pinfunction "1_1") (pintype "passive"))
      (node (ref "P2") (pin "18") (pinfunction "18_18") (pintype "passive"))
      (node (ref "P4") (pin "4") (pinfunction "4_4") (pintype "passive"))
      (node (ref "P5") (pin "3") (pinfunction "3_3") (pintype "passive"))
      (node (ref "PB1") (pin "1") (pinfunction "1_1") (pintype "bidirectional"))
      (node (ref "PB1") (pin "2") (pinfunction "2_2") (pintype "bidirectional"))
      (node (ref "R13") (pin "2") (pinfunction "2_2") (pintype "passive"))
      (node (ref "R15") (pin "2") (pinfunction "2_2") (pintype "passive"))
      (node (ref "R17") (pin "1") (pinfunction "1_1") (pintype "passive"))
      (node (ref "R18") (pin "1") (pinfunction "1_1") (pintype "passive"))
      (node (ref "R25") (pin "2") (pinfunction "2_2") (pintype "passive"))
      (node (ref "T2") (pin "2") (pinfunction "E_2") (pintype "passive"))
      (node (ref "Tp4") (pin "1") (pinfunction "1_1") (pintype "passive"))
      (node (ref "U1") (pin "13") (pinfunction "VSS_13") (pintype "output"))
      (node (ref "U2") (pin "14") (pinfunction "VSSA_14") (pintype "power_in"))
      (node (ref "U2") (pin "31") (pinfunction "VSSIO_2_31") (pintype "power_in"))
      (node (ref "U2") (pin "4") (pinfunction "VSSIO_1_4") (pintype "power_in"))
      (node (ref "U2") (pin "5") (pinfunction "VSS_5") (pintype "power_in"))
    )
    (net (code "44") (name "Net-(D1-C)") (class "Default")
      (node (ref "D1") (pin "1") (pinfunction "C_1") (pintype "passive"))
      (node (ref "IC1") (pin "1") (pinfunction "VIN_1") (pintype "input"))
    )
    (net (code "45") (name "Net-(D2-C)") (class "Default")
      (node (ref "D2") (pin "1") (pinfunction "C_1") (pintype "passive"))
      (node (ref "IC1") (pin "2") (pinfunction "OUT_2") (pintype "power_in"))
      (node (ref "L1") (pin "1") (pinfunction "1_1") (pintype "passive"))
    )
    (net (code "46") (name "Net-(D3-C)") (class "Default")
      (node (ref "D3") (pin "1") (pinfunction "C_1") (pintype "passive"))
      (node (ref "R5") (pin "1") (pinfunction "1_1") (pintype "passive"))
    )
    (net (code "47") (name "Net-(LD1-A)") (class "Default")
      (node (ref "LD1") (pin "2") (pinfunction "A_2") (pintype "passive"))
      (node (ref "R4") (pin "1") (pinfunction "1_1") (pintype "passive"))
    )
    (net (code "48") (name "Net-(LD2-A)") (class "Default")
      (node (ref "LD2") (pin "2") (pinfunction "A_2") (pintype "passive"))
      (node (ref "R9") (pin "1") (pinfunction "1_1") (pintype "passive"))
    )
    (net (code "49") (name "Net-(LD5-A)") (class "Default")
      (node (ref "LD5") (pin "2") (pinfunction "A_2") (pintype "passive"))
      (node (ref "R11") (pin "1") (pinfunction "1_1") (pintype "passive"))
    )
    (net (code "50") (name "Net-(LD10-C)") (class "Default")
      (node (ref "LD10") (pin "1") (pinfunction "C_1") (pintype "passive"))
      (node (ref "LD11") (pin "1") (pinfunction "C_1") (pintype "passive"))
      (node (ref "LD3") (pin "1") (pinfunction "C_1") (pintype "passive"))
      (node (ref "LD4") (pin "1") (pinfunction "C_1") (pintype "passive"))
      (node (ref "LD6") (pin "1") (pinfunction "C_1") (pintype "passive"))
      (node (ref "LD7") (pin "1") (pinfunction "C_1") (pintype "passive"))
      (node (ref "LD8") (pin "1") (pinfunction "C_1") (pintype "passive"))
      (node (ref "LD9") (pin "1") (pinfunction "C_1") (pintype "passive"))
      (node (ref "T1") (pin "2") (pinfunction "C_2") (pintype "open_collector"))
    )
    (net (code "51") (name "Net-(P1-Pad2)") (class "Default")
      (node (ref "P1") (pin "2") (pinfunction "2_2") (pintype "passive"))
      (node (ref "R2") (pin "2") (pinfunction "2_2") (pintype "passive"))
    )
    (net (code "52") (name "Net-(P1-Pad4)") (class "Default")
      (node (ref "P1") (pin "4") (pinfunction "4_4") (pintype "passive"))
      (node (ref "R3") (pin "2") (pinfunction "2_2") (pintype "passive"))
    )
    (net (code "53") (name "Net-(P3-Pad1)") (class "Default")
      (node (ref "P3") (pin "1") (pinfunction "1_1") (pintype "passive"))
      (node (ref "R20") (pin "1") (pinfunction "1_1") (pintype "passive"))
    )
    (net (code "54") (name "Net-(P3-Pad2)") (class "Default")
      (node (ref "P3") (pin "2") (pinfunction "2_2") (pintype "passive"))
      (node (ref "R21") (pin "1") (pinfunction "1_1") (pintype "passive"))
    )
    (net (code "55") (name "Net-(P3-Pad3)") (class "Default")
      (node (ref "P3") (pin "3") (pinfunction "3_3") (pintype "passive"))
      (node (ref "R22") (pin "1") (pinfunction "1_1") (pintype "passive"))
    )
    (net (code "56") (name "Net-(P3-Pad4)") (class "Default")
      (node (ref "P3") (pin "4") (pinfunction "4_4") (pintype "passive"))
      (node (ref "R23") (pin "1") (pinfunction "1_1") (pintype "passive"))
    )
    (net (code "57") (name "Net-(P3-Pad5)") (class "Default")
      (node (ref "P3") (pin "5") (pinfunction "5_5") (pintype "passive"))
      (node (ref "R24") (pin "1") (pinfunction "1_1") (pintype "passive"))
    )
    (net (code "58") (name "Net-(P3-Pad6)") (class "Default")
      (node (ref "P3") (pin "6") (pinfunction "6_6") (pintype "passive"))
      (node (ref "R25") (pin "1") (pinfunction "1_1") (pintype "passive"))
    )
    (net (code "59") (name "Net-(T1-B)") (class "Default")
      (node (ref "C13") (pin "1") (pinfunction "1_1") (pintype "passive"))
      (node (ref "R12") (pin "1") (pinfunction "1_1") (pintype "passive"))
      (node (ref "R13") (pin "1") (pinfunction "1_1") (pintype "passive"))
      (node (ref "T1") (pin "1") (pinfunction "B_1") (pintype "passive"))
    )
    (net (code "60") (name "Net-(T1-E)") (class "Default")
      (node (ref "R15") (pin "1") (pinfunction "1_1") (pintype "passive"))
      (node (ref "T1") (pin "3") (pinfunction "E_3") (pintype "open_emitter"))
    )
    (net (code "61") (name "Net-(T2-B)") (class "Default")
      (node (ref "R27") (pin "1") (pinfunction "1_1") (pintype "passive"))
      (node (ref "T2") (pin "1") (pinfunction "B_1") (pintype "passive"))
    )
    (net (code "62") (name "Net-(U2A-PD6{slash}UART2_RX)") (class "Default")
      (node (ref "R19") (pin "2") (pinfunction "2_2") (pintype "passive"))
      (node (ref "U2") (pin "47") (pinfunction "PD6/UART2_RX_47") (pintype "bidirectional"))
    )
    (net (code "63") (name "Net-(Y1-OSC1)") (class "Default")
      (node (ref "C10") (pin "2") (pinfunction "2_2") (pintype "passive"))
      (node (ref "R7") (pin "2") (pinfunction "2_2") (pintype "passive"))
      (node (ref "Y1") (pin "1") (pinfunction "OSC1_1") (pintype "passive"))
    )
    (net (code "64") (name "Net-(Y1-OSC2)") (class "Default")
      (node (ref "C11") (pin "2") (pinfunction "2_2") (pintype "passive"))
      (node (ref "R8") (pin "2") (pinfunction "2_2") (pintype "passive"))
      (node (ref "Y1") (pin "2") (pinfunction "OSC2_2") (pintype "passive"))
    )
    (net (code "65") (name "VDDA") (class "Default")
      (node (ref "C1") (pin "1") (pinfunction "1_1") (pintype "passive"))
      (node (ref "C2") (pin "1") (pinfunction "1_1") (pintype "passive"))
      (node (ref "FB1") (pin "2") (pinfunction "2_2") (pintype "passive"))
      (node (ref "U2") (pin "13") (pinfunction "VDDA_13") (pintype "power_in"))
    )
    (net (code "66") (name "unconnected-(U1-BZ-Pad19)") (class "Default")
      (node (ref "U1") (pin "19") (pinfunction "BZ_19") (pintype "passive"))
    )
    (net (code "67") (name "unconnected-(U1-OSCI-Pad15)") (class "Default")
      (node (ref "U1") (pin "15") (pinfunction "OSCI_15") (pintype "passive"))
    )
    (net (code "68") (name "unconnected-(U1-OSCO-Pad14)") (class "Default")
      (node (ref "U1") (pin "14") (pinfunction "OSCO_14") (pintype "power_in"))
    )
    (net (code "69") (name "unconnected-(U1-SEG12-Pad44)") (class "Default")
      (node (ref "U1") (pin "44") (pinfunction "SEG12_44") (pintype "input"))
    )
    (net (code "70") (name "unconnected-(U1-SEG13-Pad43)") (class "Default")
      (node (ref "U1") (pin "43") (pinfunction "SEG13_43") (pintype "input"))
    )
    (net (code "71") (name "unconnected-(U1-SEG14-Pad42)") (class "Default")
      (node (ref "U1") (pin "42") (pinfunction "SEG14_42") (pintype "input"))
    )
    (net (code "72") (name "unconnected-(U1-SEG15-Pad41)") (class "Default")
      (node (ref "U1") (pin "41") (pinfunction "SEG15_41") (pintype "input"))
    )
    (net (code "73") (name "unconnected-(U1-SEG16-Pad40)") (class "Default")
      (node (ref "U1") (pin "40") (pinfunction "SEG16_40") (pintype "output"))
    )
    (net (code "74") (name "unconnected-(U1-SEG17-Pad39)") (class "Default")
      (node (ref "U1") (pin "39") (pinfunction "SEG17_39") (pintype "output"))
    )
    (net (code "75") (name "unconnected-(U1-SEG18-Pad38)") (class "Default")
      (node (ref "U1") (pin "38") (pinfunction "SEG18_38") (pintype "output"))
    )
    (net (code "76") (name "unconnected-(U1-SEG19-Pad37)") (class "Default")
      (node (ref "U1") (pin "37") (pinfunction "SEG19_37") (pintype "output"))
    )
    (net (code "77") (name "unconnected-(U1-SEG20-Pad36)") (class "Default")
      (node (ref "U1") (pin "36") (pinfunction "SEG20_36") (pintype "input"))
    )
    (net (code "78") (name "unconnected-(U1-SEG21-Pad35)") (class "Default")
      (node (ref "U1") (pin "35") (pinfunction "SEG21_35") (pintype "input"))
    )
    (net (code "79") (name "unconnected-(U1-SEG22-Pad34)") (class "Default")
      (node (ref "U1") (pin "34") (pinfunction "SEG22_34") (pintype "input"))
    )
    (net (code "80") (name "unconnected-(U1-SEG23-Pad33)") (class "Default")
      (node (ref "U1") (pin "33") (pinfunction "SEG23_33") (pintype "input"))
    )
    (net (code "81") (name "unconnected-(U1-SEG24-Pad32)") (class "Default")
      (node (ref "U1") (pin "32") (pinfunction "SEG24_32") (pintype "output"))
    )
    (net (code "82") (name "unconnected-(U1-SEG25-Pad31)") (class "Default")
      (node (ref "U1") (pin "31") (pinfunction "SEG25_31") (pintype "output"))
    )
    (net (code "83") (name "unconnected-(U1-SEG26-Pad30)") (class "Default")
      (node (ref "U1") (pin "30") (pinfunction "SEG26_30") (pintype "power_in"))
    )
    (net (code "84") (name "unconnected-(U1-SEG27-Pad29)") (class "Default")
      (node (ref "U1") (pin "29") (pinfunction "SEG27_29") (pintype "power_in"))
    )
    (net (code "85") (name "unconnected-(U1-SEG28-Pad28)") (class "Default")
      (node (ref "U1") (pin "28") (pinfunction "SEG28_28") (pintype "power_in"))
    )
    (net (code "86") (name "unconnected-(U1-SEG29-Pad27)") (class "Default")
      (node (ref "U1") (pin "27") (pinfunction "SEG29_27") (pintype "power_in"))
    )
    (net (code "87") (name "unconnected-(U1-SEG30-Pad26)") (class "Default")
      (node (ref "U1") (pin "26") (pinfunction "SEG30_26") (pintype "power_in"))
    )
    (net (code "88") (name "unconnected-(U1-SEG31-Pad25)") (class "Default")
      (node (ref "U1") (pin "25") (pinfunction "SEG31_25") (pintype "power_in"))
    )
    (net (code "89") (name "unconnected-(U1-~{BZ}-Pad20)") (class "Default")
      (node (ref "U1") (pin "20") (pinfunction "~{BZ}_20") (pintype "passive"))
    )
    (net (code "90") (name "unconnected-(U1-~{IRQ}-Pad18)") (class "Default")
      (node (ref "U1") (pin "18") (pinfunction "~{IRQ}_18") (pintype "power_in"))
    )
    (net (code "91") (name "unconnected-(U2A-(HS)_PA4-Pad10)") (class "Default")
      (node (ref "U2") (pin "10") (pinfunction "(HS)_PA4_10") (pintype "bidirectional"))
    )
    (net (code "92") (name "unconnected-(U2A-(HS)_PA5-Pad11)") (class "Default")
      (node (ref "U2") (pin "11") (pinfunction "(HS)_PA5_11") (pintype "bidirectional"))
    )
    (net (code "93") (name "unconnected-(U2A-(HS)_PA6-Pad12)") (class "Default")
      (node (ref "U2") (pin "12") (pinfunction "(HS)_PA6_12") (pintype "bidirectional"))
    )
    (net (code "94") (name "unconnected-(U2A-AIN8{slash}PE7-Pad23)") (class "Default")
      (node (ref "U2") (pin "23") (pinfunction "AIN8/PE7_23") (pintype "bidirectional"))
    )
    (net (code "95") (name "unconnected-(U2A-AIN9{slash}PE6-Pad24)") (class "Default")
      (node (ref "U2") (pin "24") (pinfunction "AIN9/PE6_24") (pintype "bidirectional"))
    )
    (net (code "96") (name "unconnected-(U2A-PC1_(HS)_{slash}TIM1_CH1{slash}UART2_CK-Pad26)") (class "Default")
      (node (ref "U2") (pin "26") (pinfunction "PC1_(HS)_/TIM1_CH1/UART2_CK_26") (pintype "bidirectional"))
    )
    (net (code "97") (name "unconnected-(U2A-PC2_(HS)_{slash}TIM1_CH2-Pad27)") (class "Default")
      (node (ref "U2") (pin "27") (pinfunction "PC2_(HS)_/TIM1_CH2_27") (pintype "bidirectional"))
    )
    (net (code "98") (name "unconnected-(U2A-PC3_(HS)_{slash}TIM1_CH3-Pad28)") (class "Default")
      (node (ref "U2") (pin "28") (pinfunction "PC3_(HS)_/TIM1_CH3_28") (pintype "bidirectional"))
    )
    (net (code "99") (name "unconnected-(U2A-PC4_(HS)_{slash}TIM1_CH4-Pad29)") (class "Default")
      (node (ref "U2") (pin "29") (pinfunction "PC4_(HS)_/TIM1_CH4_29") (pintype "bidirectional"))
    )
    (net (code "100") (name "unconnected-(U2A-PD0_(HS){slash}TIM3_CH2_[TIM1_BKIN]_[CLK_CCO]-Pad41)") (class "Default")
      (node (ref "U2") (pin "41") (pinfunction "PD0_(HS)/TIM3_CH2_[TIM1_BKIN]_[CLK_CCO]_41") (pintype "bidirectional"))
    )
    (net (code "101") (name "unconnected-(U2A-PD2_(HS){slash}TIM3_CH1_[TIM2_CH3]-Pad43)") (class "Default")
      (node (ref "U2") (pin "43") (pinfunction "PD2_(HS)/TIM3_CH1_[TIM2_CH3]_43") (pintype "bidirectional"))
    )
    (net (code "102") (name "unconnected-(U2A-PD7{slash}TLI_[TIM1_CH4)-Pad48)") (class "Default")
      (node (ref "U2") (pin "48") (pinfunction "PD7/TLI_[TIM1_CH4)_48") (pintype "bidirectional"))
    )
    (net (code "103") (name "unconnected-(U2A-PE0_(HS){slash}CLK_CCO-Pad40)") (class "Default")
      (node (ref "U2") (pin "40") (pinfunction "PE0_(HS)/CLK_CCO_40") (pintype "bidirectional"))
    )
    (net (code "104") (name "unconnected-(U2A-PE3{slash}TIM1_BKIN-Pad37)") (class "Default")
      (node (ref "U2") (pin "37") (pinfunction "PE3/TIM1_BKIN_37") (pintype "bidirectional"))
    )
    (net (code "105") (name "unconnected-(U2A-PE5{slash}SPI_NSS-Pad25)") (class "Default")
      (node (ref "U2") (pin "25") (pinfunction "PE5/SPI_NSS_25") (pintype "bidirectional"))
    )
    (net (code "106") (name "unconnected-(U2A-PG0-Pad35)") (class "Default")
      (node (ref "U2") (pin "35") (pinfunction "PG0_35") (pintype "bidirectional"))
    )
    (net (code "107") (name "unconnected-(U2A-PG1-Pad36)") (class "Default")
      (node (ref "U2") (pin "36") (pinfunction "PG1_36") (pintype "bidirectional"))
    )
    (net (code "108") (name "unconnected-(U2A-[I2C_SCL]_AIN4{slash}PB4-Pad18)") (class "Default")
      (node (ref "U2") (pin "18") (pinfunction "[I2C_SCL]_AIN4/PB4_18") (pintype "bidirectional"))
    )
    (net (code "109") (name "unconnected-(U2A-[TIM3_CH1]_TIM2_CH3{slash}PA3-Pad9)") (class "Default")
      (node (ref "U2") (pin "9") (pinfunction "[TIM3_CH1]_TIM2_CH3/PA3_9") (pintype "bidirectional"))
    )
  )
)
